# hv_io_bms.net
KiCad netlist of a schematic drawn in Altium Designer
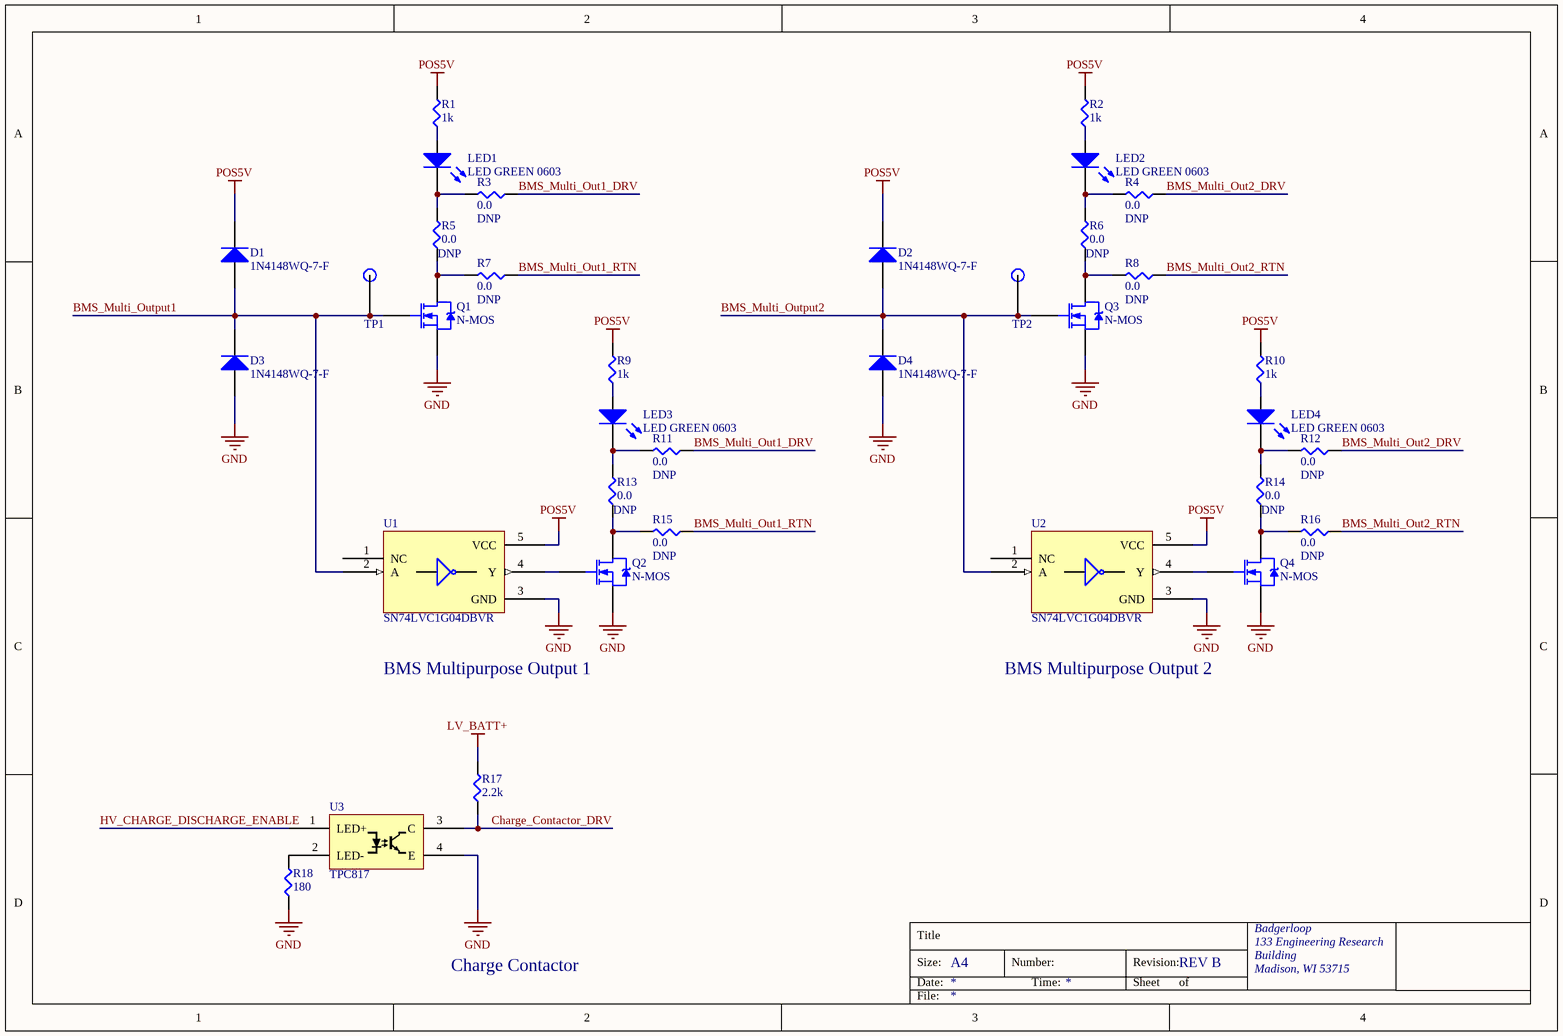
[diagram p0: hv_io_bms.SchDoc]

(export (version "E")
  (design (tool "Eeschema 10.0.6"))
  (components
    (comp (ref "D1")
      (value "1N4148WQ-7-F")
      (footprint "SODFL370X100-2N")
      (description "Diodes - General Purpose, Power, Switching SMT Fast Switching Diode")
      (fields (field (name "MANUFACTURER") "Diodes Inc."))
      (libsource (lib "temp") (part "1N4148WQ-7-F"))
    )
    (comp (ref "D2")
      (value "1N4148WQ-7-F")
      (footprint "SODFL370X100-2N")
      (description "Diodes - General Purpose, Power, Switching SMT Fast Switching Diode")
      (fields (field (name "MANUFACTURER") "Diodes Inc."))
      (libsource (lib "temp") (part "1N4148WQ-7-F"))
    )
    (comp (ref "D3")
      (value "1N4148WQ-7-F")
      (footprint "SODFL370X100-2N")
      (description "Diodes - General Purpose, Power, Switching SMT Fast Switching Diode")
      (fields (field (name "MANUFACTURER") "Diodes Inc."))
      (libsource (lib "temp") (part "1N4148WQ-7-F"))
    )
    (comp (ref "D4")
      (value "1N4148WQ-7-F")
      (footprint "SODFL370X100-2N")
      (description "Diodes - General Purpose, Power, Switching SMT Fast Switching Diode")
      (fields (field (name "MANUFACTURER") "Diodes Inc."))
      (libsource (lib "temp") (part "1N4148WQ-7-F"))
    )
    (comp (ref "LED1")
      (value "LED GREEN 0603")
      (footprint "LED 0603 GREEN")
      (fields (field (name "MANUFACTURER") "Lite-On Inc."))
      (libsource (lib "misc") (part "LED GREEN 0603"))
    )
    (comp (ref "LED2")
      (value "LED GREEN 0603")
      (footprint "LED 0603 GREEN")
      (fields (field (name "MANUFACTURER") "Lite-On Inc."))
      (libsource (lib "misc") (part "LED GREEN 0603"))
    )
    (comp (ref "LED3")
      (value "LED GREEN 0603")
      (footprint "LED 0603 GREEN")
      (fields (field (name "MANUFACTURER") "Lite-On Inc."))
      (libsource (lib "misc") (part "LED GREEN 0603"))
    )
    (comp (ref "LED4")
      (value "LED GREEN 0603")
      (footprint "LED 0603 GREEN")
      (fields (field (name "MANUFACTURER") "Lite-On Inc."))
      (libsource (lib "misc") (part "LED GREEN 0603"))
    )
    (comp (ref "Q1")
      (value "N-MOS")
      (footprint "DPAK228P991X238-3N")
      (description "N-Channel Power MOSFET, 12 A, 60 V")
      (fields (field (name "MANUFACTURER") "ON SEMI"))
      (libsource (lib "ic") (part "N-MOS"))
    )
    (comp (ref "Q2")
      (value "N-MOS")
      (footprint "DPAK228P991X238-3N")
      (description "N-Channel Power MOSFET, 12 A, 60 V")
      (fields (field (name "MANUFACTURER") "ON SEMI"))
      (libsource (lib "ic") (part "N-MOS"))
    )
    (comp (ref "Q3")
      (value "N-MOS")
      (footprint "DPAK228P991X238-3N")
      (description "N-Channel Power MOSFET, 12 A, 60 V")
      (fields (field (name "MANUFACTURER") "ON SEMI"))
      (libsource (lib "ic") (part "N-MOS"))
    )
    (comp (ref "Q4")
      (value "N-MOS")
      (footprint "DPAK228P991X238-3N")
      (description "N-Channel Power MOSFET, 12 A, 60 V")
      (fields (field (name "MANUFACTURER") "ON SEMI"))
      (libsource (lib "ic") (part "N-MOS"))
    )
    (comp (ref "R1")
      (value "1k")
      (footprint "SMD-0402-RES")
      (description "RES SMD 1K OHM 5% 1/10W 0402")
      (fields (field (name "PART NUMBER") "ERJ-2GEJ102X") (field (name "DIGI-KEY PART NUMBER") "P1.0KJCT-ND"))
      (libsource (lib "resistor") (part "ERJ-2GEJ102X"))
    )
    (comp (ref "R2")
      (value "1k")
      (footprint "SMD-0402-RES")
      (description "RES SMD 1K OHM 5% 1/10W 0402")
      (fields (field (name "PART NUMBER") "ERJ-2GEJ102X") (field (name "DIGI-KEY PART NUMBER") "P1.0KJCT-ND"))
      (libsource (lib "resistor") (part "ERJ-2GEJ102X"))
    )
    (comp (ref "R3")
      (value "0.0")
      (footprint "SMD-0402-RES")
      (description "RES SMD 0.0OHM JUMPER 1/10W 0402")
      (fields
        (field (name "PART NUMBER") "ERJ-2GE0R00X")
        (field (name "DIGI-KEY PART NUMBER") "P0.0JCT-ND")
        (field (name "DNP") "DNP")
      )
      (libsource (lib "resistor") (part "ERJ-2GE0R00X"))
    )
    (comp (ref "R4")
      (value "0.0")
      (footprint "SMD-0402-RES")
      (description "RES SMD 0.0OHM JUMPER 1/10W 0402")
      (fields
        (field (name "PART NUMBER") "ERJ-2GE0R00X")
        (field (name "DIGI-KEY PART NUMBER") "P0.0JCT-ND")
        (field (name "DNP") "DNP")
      )
      (libsource (lib "resistor") (part "ERJ-2GE0R00X"))
    )
    (comp (ref "R5")
      (value "0.0")
      (footprint "SMD-0402-RES")
      (description "RES SMD 0.0OHM JUMPER 1/10W 0402")
      (fields
        (field (name "PART NUMBER") "ERJ-2GE0R00X")
        (field (name "DIGI-KEY PART NUMBER") "P0.0JCT-ND")
        (field (name "DNP") "DNP")
      )
      (libsource (lib "resistor") (part "ERJ-2GE0R00X"))
    )
    (comp (ref "R6")
      (value "0.0")
      (footprint "SMD-0402-RES")
      (description "RES SMD 0.0OHM JUMPER 1/10W 0402")
      (fields
        (field (name "PART NUMBER") "ERJ-2GE0R00X")
        (field (name "DIGI-KEY PART NUMBER") "P0.0JCT-ND")
        (field (name "DNP") "DNP")
      )
      (libsource (lib "resistor") (part "ERJ-2GE0R00X"))
    )
    (comp (ref "R7")
      (value "0.0")
      (footprint "SMD-0402-RES")
      (description "RES SMD 0.0OHM JUMPER 1/10W 0402")
      (fields
        (field (name "PART NUMBER") "ERJ-2GE0R00X")
        (field (name "DIGI-KEY PART NUMBER") "P0.0JCT-ND")
        (field (name "DNP") "DNP")
      )
      (libsource (lib "resistor") (part "ERJ-2GE0R00X"))
    )
    (comp (ref "R8")
      (value "0.0")
      (footprint "SMD-0402-RES")
      (description "RES SMD 0.0OHM JUMPER 1/10W 0402")
      (fields
        (field (name "PART NUMBER") "ERJ-2GE0R00X")
        (field (name "DIGI-KEY PART NUMBER") "P0.0JCT-ND")
        (field (name "DNP") "DNP")
      )
      (libsource (lib "resistor") (part "ERJ-2GE0R00X"))
    )
    (comp (ref "R9")
      (value "1k")
      (footprint "SMD-0402-RES")
      (description "RES SMD 1K OHM 5% 1/10W 0402")
      (fields (field (name "PART NUMBER") "ERJ-2GEJ102X") (field (name "DIGI-KEY PART NUMBER") "P1.0KJCT-ND"))
      (libsource (lib "resistor") (part "ERJ-2GEJ102X"))
    )
    (comp (ref "R10")
      (value "1k")
      (footprint "SMD-0402-RES")
      (description "RES SMD 1K OHM 5% 1/10W 0402")
      (fields (field (name "PART NUMBER") "ERJ-2GEJ102X") (field (name "DIGI-KEY PART NUMBER") "P1.0KJCT-ND"))
      (libsource (lib "resistor") (part "ERJ-2GEJ102X"))
    )
    (comp (ref "R11")
      (value "0.0")
      (footprint "SMD-0402-RES")
      (description "RES SMD 0.0OHM JUMPER 1/10W 0402")
      (fields
        (field (name "PART NUMBER") "ERJ-2GE0R00X")
        (field (name "DIGI-KEY PART NUMBER") "P0.0JCT-ND")
        (field (name "DNP") "DNP")
      )
      (libsource (lib "resistor") (part "ERJ-2GE0R00X"))
    )
    (comp (ref "R12")
      (value "0.0")
      (footprint "SMD-0402-RES")
      (description "RES SMD 0.0OHM JUMPER 1/10W 0402")
      (fields
        (field (name "PART NUMBER") "ERJ-2GE0R00X")
        (field (name "DIGI-KEY PART NUMBER") "P0.0JCT-ND")
        (field (name "DNP") "DNP")
      )
      (libsource (lib "resistor") (part "ERJ-2GE0R00X"))
    )
    (comp (ref "R13")
      (value "0.0")
      (footprint "SMD-0402-RES")
      (description "RES SMD 0.0OHM JUMPER 1/10W 0402")
      (fields
        (field (name "PART NUMBER") "ERJ-2GE0R00X")
        (field (name "DIGI-KEY PART NUMBER") "P0.0JCT-ND")
        (field (name "DNP") "DNP")
      )
      (libsource (lib "resistor") (part "ERJ-2GE0R00X"))
    )
    (comp (ref "R14")
      (value "0.0")
      (footprint "SMD-0402-RES")
      (description "RES SMD 0.0OHM JUMPER 1/10W 0402")
      (fields
        (field (name "PART NUMBER") "ERJ-2GE0R00X")
        (field (name "DIGI-KEY PART NUMBER") "P0.0JCT-ND")
        (field (name "DNP") "DNP")
      )
      (libsource (lib "resistor") (part "ERJ-2GE0R00X"))
    )
    (comp (ref "R15")
      (value "0.0")
      (footprint "SMD-0402-RES")
      (description "RES SMD 0.0OHM JUMPER 1/10W 0402")
      (fields
        (field (name "PART NUMBER") "ERJ-2GE0R00X")
        (field (name "DIGI-KEY PART NUMBER") "P0.0JCT-ND")
        (field (name "DNP") "DNP")
      )
      (libsource (lib "resistor") (part "ERJ-2GE0R00X"))
    )
    (comp (ref "R16")
      (value "0.0")
      (footprint "SMD-0402-RES")
      (description "RES SMD 0.0OHM JUMPER 1/10W 0402")
      (fields
        (field (name "PART NUMBER") "ERJ-2GE0R00X")
        (field (name "DIGI-KEY PART NUMBER") "P0.0JCT-ND")
        (field (name "DNP") "DNP")
      )
      (libsource (lib "resistor") (part "ERJ-2GE0R00X"))
    )
    (comp (ref "R17")
      (value "2.2k")
      (footprint "SMD-1206-RES")
      (description "RES SMD 2.2K OHM 1% 1/4W 1206")
      (fields
        (field (name "PART NUMBER") "ERJ-8ENF2201V")
        (field (name "DIGI-KEY PART NUMBER") "P2.20KFCT-ND")
      )
      (libsource (lib "resistor") (part "ERJ-8ENF2201V"))
    )
    (comp (ref "R18")
      (value "180")
      (footprint "SMD-1206-RES")
      (description "RES SMD 180 OHM 1% 1/4W 1206")
      (fields (field (name "PART NUMBER") "ERJ-8ENF1800V") (field (name "DIGI-KEY PART NUMBER") "P180FCT-ND"))
      (libsource (lib "resistor") (part "ERJ-8ENF1800V"))
    )
    (comp (ref "TP1") (value "TP") (footprint "Test Point") (libsource (lib "misc") (part "TP")))
    (comp (ref "TP2") (value "TP") (footprint "Test Point") (libsource (lib "misc") (part "TP")))
    (comp (ref "U1")
      (value "SN74LVC1G04DBVR")
      (footprint "DBV5-L")
      (fields (field (name "MANUFACTURER") "TI"))
      (libsource (lib "temp") (part "SN74LVC1G04DBVR"))
    )
    (comp (ref "U2")
      (value "SN74LVC1G04DBVR")
      (footprint "DBV5-L")
      (fields (field (name "MANUFACTURER") "TI"))
      (libsource (lib "temp") (part "SN74LVC1G04DBVR"))
    )
    (comp (ref "U3")
      (value "TPC817")
      (footprint "SOT200P1005X328-5N")
      (description "OPTOISO 5KV TRANS 4SOP")
      (fields (field (name "MANUFACTURER") "Taiwan Semi"))
      (libsource (lib "ic") (part "TPC817"))
    )
  )
  (nets
    (net (code "1") (name "/BMS_Multi_Out1_DRV") (class "Default")
      (node (ref "R11") (pin "1") (pinfunction "1_1") (pintype "passive"))
      (node (ref "R3") (pin "1") (pinfunction "1_1") (pintype "passive"))
    )
    (net (code "2") (name "/BMS_Multi_Out1_RTN") (class "Default")
      (node (ref "R15") (pin "1") (pinfunction "1_1") (pintype "passive"))
      (node (ref "R7") (pin "1") (pinfunction "1_1") (pintype "passive"))
    )
    (net (code "3") (name "/BMS_Multi_Out2_DRV") (class "Default")
      (node (ref "R12") (pin "1") (pinfunction "1_1") (pintype "passive"))
      (node (ref "R4") (pin "1") (pinfunction "1_1") (pintype "passive"))
    )
    (net (code "4") (name "/BMS_Multi_Out2_RTN") (class "Default")
      (node (ref "R16") (pin "1") (pinfunction "1_1") (pintype "passive"))
      (node (ref "R8") (pin "1") (pinfunction "1_1") (pintype "passive"))
    )
    (net (code "5") (name "/BMS_Multi_Output1") (class "Default")
      (node (ref "D1") (pin "1") (pinfunction "A_1") (pintype "passive"))
      (node (ref "D3") (pin "2") (pinfunction "K_2") (pintype "passive"))
      (node (ref "Q1") (pin "1") (pinfunction "G_1") (pintype "passive"))
      (node (ref "TP1") (pin "1") (pinfunction "1_1") (pintype "passive"))
      (node (ref "U1") (pin "2") (pinfunction "A_2") (pintype "input"))
    )
    (net (code "6") (name "/BMS_Multi_Output2") (class "Default")
      (node (ref "D2") (pin "1") (pinfunction "A_1") (pintype "passive"))
      (node (ref "D4") (pin "2") (pinfunction "K_2") (pintype "passive"))
      (node (ref "Q3") (pin "1") (pinfunction "G_1") (pintype "passive"))
      (node (ref "TP2") (pin "1") (pinfunction "1_1") (pintype "passive"))
      (node (ref "U2") (pin "2") (pinfunction "A_2") (pintype "input"))
    )
    (net (code "7") (name "/Charge_Contactor_DRV") (class "Default")
      (node (ref "R17") (pin "1") (pinfunction "1_1") (pintype "passive"))
      (node (ref "U3") (pin "3") (pinfunction "C_3") (pintype "passive"))
    )
    (net (code "8") (name "/HV_CHARGE_DISCHARGE_ENABLE") (class "Default")
      (node (ref "U3") (pin "1") (pinfunction "LED+_1") (pintype "passive"))
    )
    (net (code "9") (name "GND") (class "Default")
      (node (ref "D3") (pin "1") (pinfunction "A_1") (pintype "passive"))
      (node (ref "D4") (pin "1") (pinfunction "A_1") (pintype "passive"))
      (node (ref "Q1") (pin "3") (pinfunction "S_3") (pintype "passive"))
      (node (ref "Q2") (pin "3") (pinfunction "S_3") (pintype "passive"))
      (node (ref "Q3") (pin "3") (pinfunction "S_3") (pintype "passive"))
      (node (ref "Q4") (pin "3") (pinfunction "S_3") (pintype "passive"))
      (node (ref "R18") (pin "1") (pinfunction "1_1") (pintype "passive"))
      (node (ref "U1") (pin "3") (pinfunction "GND_3") (pintype "power_in"))
      (node (ref "U2") (pin "3") (pinfunction "GND_3") (pintype "power_in"))
      (node (ref "U3") (pin "4") (pinfunction "E_4") (pintype "passive"))
    )
    (net (code "10") (name "LV_BATT+") (class "Default")
      (node (ref "R17") (pin "2") (pinfunction "2_2") (pintype "passive"))
    )
    (net (code "11") (name "Net-(LED1-A)") (class "Default")
      (node (ref "LED1") (pin "1") (pinfunction "A_1") (pintype "passive"))
      (node (ref "R1") (pin "1") (pinfunction "1_1") (pintype "passive"))
    )
    (net (code "12") (name "Net-(LED1-K)") (class "Default")
      (node (ref "LED1") (pin "2") (pinfunction "K_2") (pintype "passive"))
      (node (ref "R3") (pin "2") (pinfunction "2_2") (pintype "passive"))
      (node (ref "R5") (pin "2") (pinfunction "2_2") (pintype "passive"))
    )
    (net (code "13") (name "Net-(LED2-A)") (class "Default")
      (node (ref "LED2") (pin "1") (pinfunction "A_1") (pintype "passive"))
      (node (ref "R2") (pin "1") (pinfunction "1_1") (pintype "passive"))
    )
    (net (code "14") (name "Net-(LED2-K)") (class "Default")
      (node (ref "LED2") (pin "2") (pinfunction "K_2") (pintype "passive"))
      (node (ref "R4") (pin "2") (pinfunction "2_2") (pintype "passive"))
      (node (ref "R6") (pin "2") (pinfunction "2_2") (pintype "passive"))
    )
    (net (code "15") (name "Net-(LED3-A)") (class "Default")
      (node (ref "LED3") (pin "1") (pinfunction "A_1") (pintype "passive"))
      (node (ref "R9") (pin "1") (pinfunction "1_1") (pintype "passive"))
    )
    (net (code "16") (name "Net-(LED3-K)") (class "Default")
      (node (ref "LED3") (pin "2") (pinfunction "K_2") (pintype "passive"))
      (node (ref "R11") (pin "2") (pinfunction "2_2") (pintype "passive"))
      (node (ref "R13") (pin "2") (pinfunction "2_2") (pintype "passive"))
    )
    (net (code "17") (name "Net-(LED4-A)") (class "Default")
      (node (ref "LED4") (pin "1") (pinfunction "A_1") (pintype "passive"))
      (node (ref "R10") (pin "1") (pinfunction "1_1") (pintype "passive"))
    )
    (net (code "18") (name "Net-(LED4-K)") (class "Default")
      (node (ref "LED4") (pin "2") (pinfunction "K_2") (pintype "passive"))
      (node (ref "R12") (pin "2") (pinfunction "2_2") (pintype "passive"))
      (node (ref "R14") (pin "2") (pinfunction "2_2") (pintype "passive"))
    )
    (net (code "19") (name "Net-(Q1-D)") (class "Default")
      (node (ref "Q1") (pin "4") (pinfunction "D_4") (pintype "passive"))
      (node (ref "R5") (pin "1") (pinfunction "1_1") (pintype "passive"))
      (node (ref "R7") (pin "2") (pinfunction "2_2") (pintype "passive"))
    )
    (net (code "20") (name "Net-(Q2-D)") (class "Default")
      (node (ref "Q2") (pin "4") (pinfunction "D_4") (pintype "passive"))
      (node (ref "R13") (pin "1") (pinfunction "1_1") (pintype "passive"))
      (node (ref "R15") (pin "2") (pinfunction "2_2") (pintype "passive"))
    )
    (net (code "21") (name "Net-(Q2-G)") (class "Default")
      (node (ref "Q2") (pin "1") (pinfunction "G_1") (pintype "passive"))
      (node (ref "U1") (pin "4") (pinfunction "Y_4") (pintype "output"))
    )
    (net (code "22") (name "Net-(Q3-D)") (class "Default")
      (node (ref "Q3") (pin "4") (pinfunction "D_4") (pintype "passive"))
      (node (ref "R6") (pin "1") (pinfunction "1_1") (pintype "passive"))
      (node (ref "R8") (pin "2") (pinfunction "2_2") (pintype "passive"))
    )
    (net (code "23") (name "Net-(Q4-D)") (class "Default")
      (node (ref "Q4") (pin "4") (pinfunction "D_4") (pintype "passive"))
      (node (ref "R14") (pin "1") (pinfunction "1_1") (pintype "passive"))
      (node (ref "R16") (pin "2") (pinfunction "2_2") (pintype "passive"))
    )
    (net (code "24") (name "Net-(Q4-G)") (class "Default")
      (node (ref "Q4") (pin "1") (pinfunction "G_1") (pintype "passive"))
      (node (ref "U2") (pin "4") (pinfunction "Y_4") (pintype "output"))
    )
    (net (code "25") (name "Net-(U3-LED-)") (class "Default")
      (node (ref "R18") (pin "2") (pinfunction "2_2") (pintype "passive"))
      (node (ref "U3") (pin "2") (pinfunction "LED-_2") (pintype "passive"))
    )
    (net (code "26") (name "POS5V") (class "Default")
      (node (ref "D1") (pin "2") (pinfunction "K_2") (pintype "passive"))
      (node (ref "D2") (pin "2") (pinfunction "K_2") (pintype "passive"))
      (node (ref "R1") (pin "2") (pinfunction "2_2") (pintype "passive"))
      (node (ref "R10") (pin "2") (pinfunction "2_2") (pintype "passive"))
      (node (ref "R2") (pin "2") (pinfunction "2_2") (pintype "passive"))
      (node (ref "R9") (pin "2") (pinfunction "2_2") (pintype "passive"))
      (node (ref "U1") (pin "5") (pinfunction "VCC_5") (pintype "power_in"))
      (node (ref "U2") (pin "5") (pinfunction "VCC_5") (pintype "power_in"))
    )
    (net (code "27") (name "unconnected-(U1-NC-Pad1)") (class "Default")
      (node (ref "U1") (pin "1") (pinfunction "NC_1") (pintype "passive"))
    )
    (net (code "28") (name "unconnected-(U2-NC-Pad1)") (class "Default")
      (node (ref "U2") (pin "1") (pinfunction "NC_1") (pintype "passive"))
    )
  )
)
